# Power.net
KiCad netlist of a schematic drawn in Altium Designer
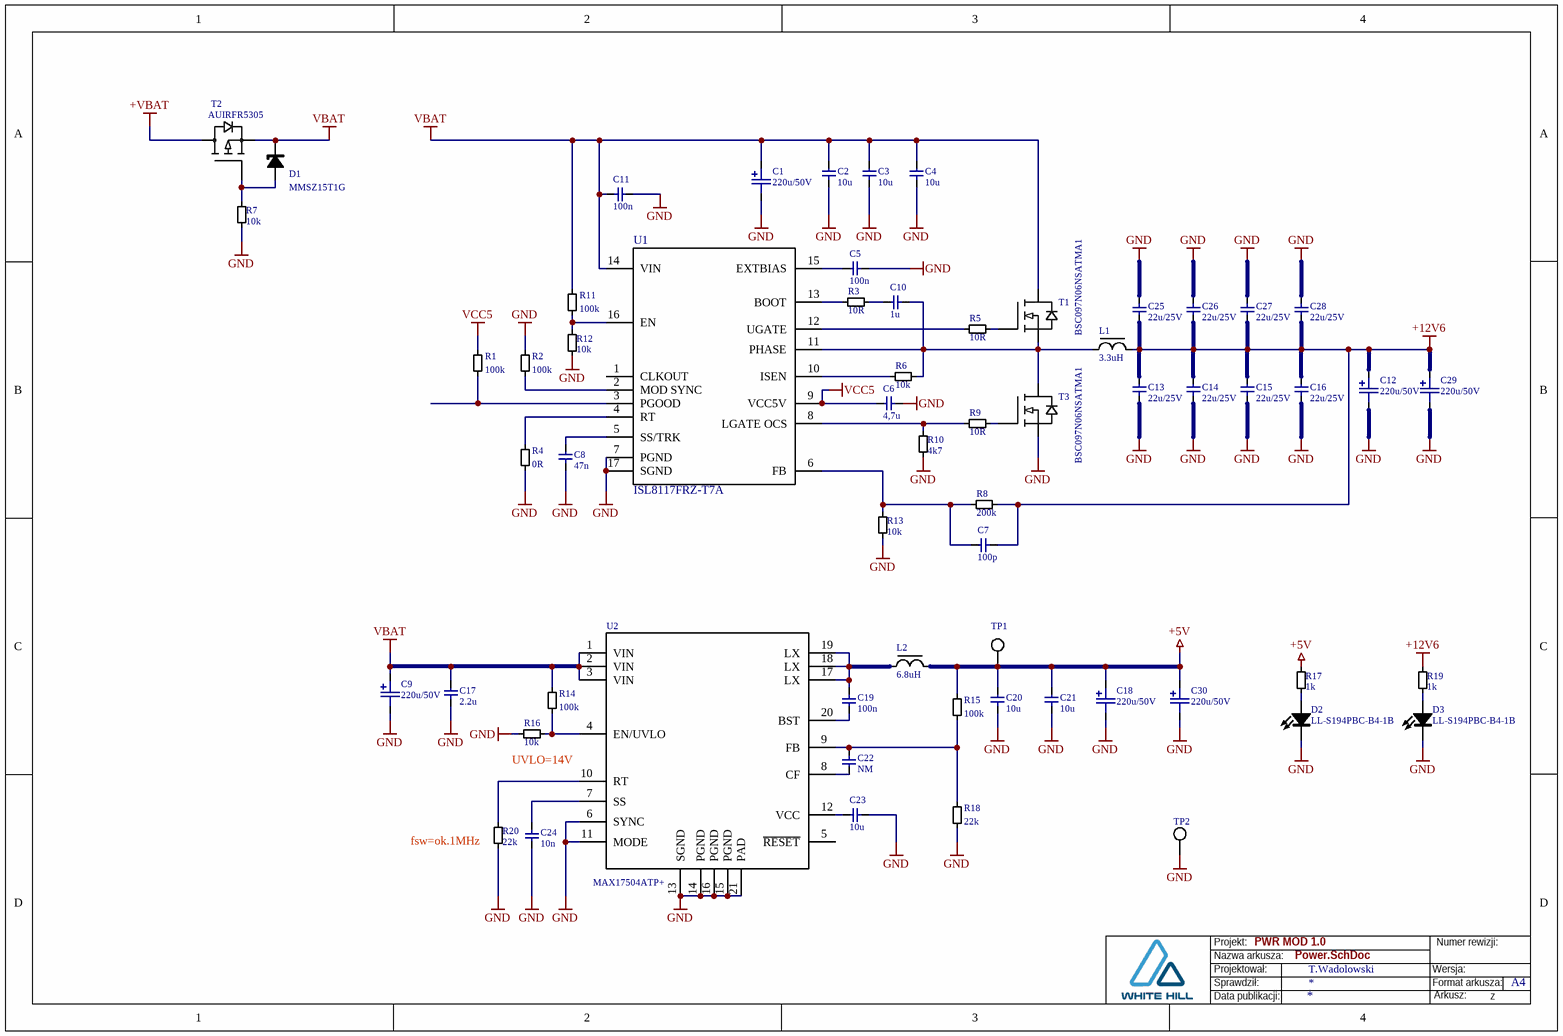
[diagram p0: Power.SchDoc]

(export (version "E")
  (design (tool "Eeschema 10.0.6"))
  (components
    (comp (ref "C1")
      (value "220u/50V")
      (footprint "ALU-G")
      (description "Capacitor: electrolytic; low impedance; 220uF; 50VDC; Case: G")
      (fields (field (name "MANUFACTURER") "Panasonic") (field (name "PART NUMBER") "EEEFP1H221AP"))
      (libsource (lib "WH") (part "CAP-EL"))
    )
    (comp (ref "C2")
      (value "10u")
      (footprint "C1206")
      (description "Capacitor: ceramic; 10uF; 50V; X7R; ±10%; SMD; 1206")
      (fields (field (name "MANUFACTURER") "Samnsung") (field (name "PART NUMBER") "CL31A106KBHNNNE"))
      (libsource (lib "CAPcer") (part "C-028"))
    )
    (comp (ref "C3")
      (value "10u")
      (footprint "C1206")
      (description "Capacitor: ceramic; 10uF; 50V; X7R; ±10%; SMD; 1206")
      (fields (field (name "MANUFACTURER") "Samnsung") (field (name "PART NUMBER") "CL31A106KBHNNNE"))
      (libsource (lib "CAPcer") (part "C-028"))
    )
    (comp (ref "C4")
      (value "10u")
      (footprint "C1206")
      (description "Capacitor: ceramic; 10uF; 50V; X7R; ±10%; SMD; 1206")
      (fields (field (name "MANUFACTURER") "Samnsung") (field (name "PART NUMBER") "CL31A106KBHNNNE"))
      (libsource (lib "CAPcer") (part "C-028"))
    )
    (comp (ref "C5")
      (value "100n")
      (footprint "C0603")
      (description "Capacitor: ceramic; 100nF; 50V; X7R; ±10%; SMD; 0603; Series: GRM")
      (fields (field (name "MANUFACTURER") "Murata") (field (name "PART NUMBER") "GRM188R71H104KA93D"))
      (libsource (lib "CAPcer") (part "C-013"))
    )
    (comp (ref "C6")
      (value "4,7u")
      (footprint "C0603")
      (description "Capacitor: ceramic;4,7uF ; 50V; X7R; ±5%; SMD; 0603")
      (fields (field (name "MANUFACTURER") "Samsung") (field (name "PART NUMBER") "0603X475K100CT"))
      (libsource (lib "CAPcer") (part "C-031"))
    )
    (comp (ref "C7")
      (value "100p")
      (footprint "C0603")
      (description "Capacitor: ceramic; MLCC; 100pF; 50V; C0G; ±1%; SMD; 0603")
      (fields (field (name "MANUFACTURER") "Vishay") (field (name "PART NUMBER") "VJ0603A101FXACW1BC"))
      (libsource (lib "CAPcer") (part "C-005"))
    )
    (comp (ref "C8")
      (value "47n")
      (footprint "C0603")
      (description "Capacitor: ceramic; MLCC; 47nF; 50V; X7R; ±10%; SMD; 0603")
      (fields (field (name "MANUFACTURER") "Kemet") (field (name "PART NUMBER") "C0603C473K5RACTU"))
      (libsource (lib "CAPcer") (part "C-012"))
    )
    (comp (ref "C9")
      (value "220u/50V")
      (footprint "ALU-G")
      (description "Capacitor: electrolytic; low impedance; 220uF; 50VDC; Case: G")
      (fields (field (name "MANUFACTURER") "Panasonic") (field (name "PART NUMBER") "EEEFP1H221AP"))
      (libsource (lib "WH") (part "CAP-EL"))
    )
    (comp (ref "C10")
      (value "1u")
      (footprint "C0805-10")
      (description "Capacitor: ceramic; MLCC; 1uF; 50V; X7R; SMD; 0805")
      (fields (field (name "MANUFACTURER") "Samsung") (field (name "PART NUMBER") "CL21B105KBFNNNG"))
      (libsource (lib "CAPcer") (part "C-017"))
    )
    (comp (ref "C11")
      (value "100n")
      (footprint "C0603")
      (description "Capacitor: ceramic; 100nF; 50V; X7R; ±10%; SMD; 0603; Series: GRM")
      (fields (field (name "MANUFACTURER") "Murata") (field (name "PART NUMBER") "GRM188R71H104KA93D"))
      (libsource (lib "CAPcer") (part "C-013"))
    )
    (comp (ref "C12")
      (value "220u/50V")
      (footprint "ALU-G")
      (description "Capacitor: electrolytic; low impedance; 220uF; 50VDC; Case: G")
      (fields (field (name "MANUFACTURER") "Panasonic") (field (name "PART NUMBER") "EEEFP1H221AP"))
      (libsource (lib "WH") (part "CAP-EL"))
    )
    (comp (ref "C13")
      (value "22u/25V")
      (footprint "C1206")
      (description "Capacitor: ceramic; 22uF; 25V; X7R; ±10%; SMD; 1206")
      (fields (field (name "MANUFACTURER") "Murata") (field (name "PART NUMBER") "GRM31CR61E226KE15L"))
      (libsource (lib "CAPcer") (part "C-029"))
    )
    (comp (ref "C14")
      (value "22u/25V")
      (footprint "C1206")
      (description "Capacitor: ceramic; 22uF; 25V; X7R; ±10%; SMD; 1206")
      (fields (field (name "MANUFACTURER") "Murata") (field (name "PART NUMBER") "GRM31CR61E226KE15L"))
      (libsource (lib "CAPcer") (part "C-029"))
    )
    (comp (ref "C15")
      (value "22u/25V")
      (footprint "C1206")
      (description "Capacitor: ceramic; 22uF; 25V; X7R; ±10%; SMD; 1206")
      (fields (field (name "MANUFACTURER") "Murata") (field (name "PART NUMBER") "GRM31CR61E226KE15L"))
      (libsource (lib "CAPcer") (part "C-029"))
    )
    (comp (ref "C16")
      (value "22u/25V")
      (footprint "C1206")
      (description "Capacitor: ceramic; 22uF; 25V; X7R; ±10%; SMD; 1206")
      (fields (field (name "MANUFACTURER") "Murata") (field (name "PART NUMBER") "GRM31CR61E226KE15L"))
      (libsource (lib "CAPcer") (part "C-029"))
    )
    (comp (ref "C17")
      (value "2.2u")
      (footprint "C1210")
      (description "Capacitor: ceramic; MLCC; 2,2uF; 100V; X7R; ±10%; SMD; 1210")
      (fields (field (name "MANUFACTURER") "Samnsung") (field (name "PART NUMBER") "CL32B225KCJSNNE"))
      (libsource (lib "CAPcer") (part "C-020"))
    )
    (comp (ref "C18")
      (value "220u/50V")
      (footprint "ALU-G")
      (description "Capacitor: electrolytic; low impedance; 220uF; 50VDC; Case: G")
      (fields (field (name "MANUFACTURER") "Panasonic") (field (name "PART NUMBER") "EEEFP1H221AP"))
      (libsource (lib "WH") (part "CAP-EL"))
    )
    (comp (ref "C19")
      (value "100n")
      (footprint "C0603")
      (description "Capacitor: ceramic; 100nF; 50V; X7R; ±10%; SMD; 0603; Series: GRM")
      (fields (field (name "MANUFACTURER") "Murata") (field (name "PART NUMBER") "GRM188R71H104KA93D"))
      (libsource (lib "CAPcer") (part "C-013"))
    )
    (comp (ref "C20")
      (value "10u")
      (footprint "C1206")
      (description "Capacitor: ceramic; 10uF; 35V; X7R; ±10%; SMD; 1206")
      (fields (field (name "MANUFACTURER") "Samnsung") (field (name "PART NUMBER") "CL31B106KLHNNNE"))
      (libsource (lib "CAPcer") (part "C-022"))
    )
    (comp (ref "C21")
      (value "10u")
      (footprint "C1206")
      (description "Capacitor: ceramic; 10uF; 35V; X7R; ±10%; SMD; 1206")
      (fields (field (name "MANUFACTURER") "Samnsung") (field (name "PART NUMBER") "CL31B106KLHNNNE"))
      (libsource (lib "CAPcer") (part "C-022"))
    )
    (comp (ref "C22")
      (value "NM")
      (footprint "C0603")
      (fields (field (name "MANUFACTURER") "Murata"))
      (libsource (lib "CAPcer") (part "C-013"))
    )
    (comp (ref "C23")
      (value "10u")
      (footprint "C0805-10")
      (description "Capacitor: ceramic; MLCC; 10uF; 16V; X5R; ±10%; SMD; 0805")
      (fields (field (name "MANUFACTURER") "Samnsung") (field (name "PART NUMBER") "CL21A106KOQNNNG"))
      (libsource (lib "CAPcer") (part "C-019"))
    )
    (comp (ref "C24")
      (value "10n")
      (footprint "C0603")
      (description "Capacitor: ceramic; MLCC; 10nF; 50V; X7R; ±5%; SMD; 0603")
      (fields (field (name "MANUFACTURER") "Vishay") (field (name "PART NUMBER") "VJ0603Y103JXACW1BC"))
      (libsource (lib "CAPcer") (part "C-011"))
    )
    (comp (ref "C25")
      (value "22u/25V")
      (footprint "C1206")
      (description "Capacitor: ceramic; 22uF; 25V; X7R; ±10%; SMD; 1206")
      (fields (field (name "MANUFACTURER") "Murata") (field (name "PART NUMBER") "GRM31CR61E226KE15L"))
      (libsource (lib "CAPcer") (part "C-029"))
    )
    (comp (ref "C26")
      (value "22u/25V")
      (footprint "C1206")
      (description "Capacitor: ceramic; 22uF; 25V; X7R; ±10%; SMD; 1206")
      (fields (field (name "MANUFACTURER") "Murata") (field (name "PART NUMBER") "GRM31CR61E226KE15L"))
      (libsource (lib "CAPcer") (part "C-029"))
    )
    (comp (ref "C27")
      (value "22u/25V")
      (footprint "C1206")
      (description "Capacitor: ceramic; 22uF; 25V; X7R; ±10%; SMD; 1206")
      (fields (field (name "MANUFACTURER") "Murata") (field (name "PART NUMBER") "GRM31CR61E226KE15L"))
      (libsource (lib "CAPcer") (part "C-029"))
    )
    (comp (ref "C28")
      (value "22u/25V")
      (footprint "C1206")
      (description "Capacitor: ceramic; 22uF; 25V; X7R; ±10%; SMD; 1206")
      (fields (field (name "MANUFACTURER") "Murata") (field (name "PART NUMBER") "GRM31CR61E226KE15L"))
      (libsource (lib "CAPcer") (part "C-029"))
    )
    (comp (ref "C29")
      (value "220u/50V")
      (footprint "ALU-G")
      (description "Capacitor: electrolytic; low impedance; 220uF; 50VDC; Case: G")
      (fields (field (name "MANUFACTURER") "Panasonic") (field (name "PART NUMBER") "EEEFP1H221AP"))
      (libsource (lib "WH") (part "CAP-EL"))
    )
    (comp (ref "C30")
      (value "220u/50V")
      (footprint "ALU-G")
      (description "Capacitor: electrolytic; low impedance; 220uF; 50VDC; Case: G")
      (fields (field (name "MANUFACTURER") "Panasonic") (field (name "PART NUMBER") "EEEFP1H221AP"))
      (libsource (lib "WH") (part "CAP-EL"))
    )
    (comp (ref "D1")
      (value "MMSZ15T1G")
      (footprint "SOD123")
      (description "Dioda: Zenera; 0,5W; 18V; SMD")
      (fields (field (name "MANUFACTURER") "ON Semi"))
      (libsource (lib "DGI") (part "D_ZEN"))
    )
    (comp (ref "D2")
      (value "LL-S194PBC-B4-1B")
      (footprint "LED0603B")
      (description "LED; SMD; 0603; blue; 20-40mcd; 1.6x0.8x0.4mm; 130°; 2.8÷3.8V; 20mA")
      (fields (field (name "MANUFACTURER") "LuckyLight"))
      (libsource (lib "DGI") (part "LED_1"))
    )
    (comp (ref "D3")
      (value "LL-S194PBC-B4-1B")
      (footprint "LED0603B")
      (description "LED; SMD; 0603; blue; 20-40mcd; 1.6x0.8x0.4mm; 130°; 2.8÷3.8V; 20mA")
      (fields (field (name "MANUFACTURER") "LuckyLight"))
      (libsource (lib "DGI") (part "LED_1"))
    )
    (comp (ref "L1")
      (value "3.3uH")
      (footprint "HPI1260")
      (description "Inductor: wire; SMD; 3.3uH; Ioper:14A; 2.45mOhm; ±20%; Isat:15A")
      (fields (field (name "MANUFACTURER") "Ferrocore") (field (name "PART NUMBER") "HPI1260-3R3"))
      (libsource (lib "WH") (part "L_HPI_3.3uH"))
    )
    (comp (ref "L2")
      (value "6.8uH")
      (footprint "L 7x7")
      (description "Inductor: wire; SMD; 6.8uH; Ioper:4.3A; 53mΩ; ±20%; Isat:4.9A")
      (fields (field (name "MANUFACTURER") "Ferrocore") (field (name "PART NUMBER") "HPI0630-6R8"))
      (libsource (lib "DGI") (part "L"))
    )
    (comp (ref "R1")
      (value "100k")
      (footprint "R0603")
      (description "Resistor: thick film; SMD; 0603; 100k; 0.125W; ±5%")
      (fields (field (name "MANUFACTURER") "Walsin") (field (name "PART NUMBER") "WF06P104JTL"))
      (libsource (lib "Resistors") (part "R-013"))
    )
    (comp (ref "R2")
      (value "100k")
      (footprint "R0603")
      (description "Resistor: thick film; SMD; 0603; 100k; 0.125W; ±5%")
      (fields (field (name "MANUFACTURER") "Walsin") (field (name "PART NUMBER") "WF06P104JTL"))
      (libsource (lib "Resistors") (part "R-013"))
    )
    (comp (ref "R3")
      (value "10R")
      (footprint "R0603")
      (description "Resistor: thick film; SMD; 0603; 10R; 0.1W; ±5%")
      (fields (field (name "MANUFACTURER") "Royal Ohm") (field (name "PART NUMBER") "0603SAJ0100T5E"))
      (libsource (lib "Resistors") (part "R-001"))
    )
    (comp (ref "R4")
      (value "0R")
      (footprint "R0603")
      (description "Resistor: thick film; SMD; 0603; 0R; 0.125W; ±5%")
      (fields (field (name "MANUFACTURER") "Royal Ohm") (field (name "PART NUMBER") "CRCW06030000Z0TABC"))
      (libsource (lib "Resistors") (part "R-018"))
    )
    (comp (ref "R5")
      (value "10R")
      (footprint "R0603")
      (description "Resistor: thick film; SMD; 0603; 10R; 0.1W; ±5%")
      (fields (field (name "MANUFACTURER") "Royal Ohm") (field (name "PART NUMBER") "0603SAJ0100T5E"))
      (libsource (lib "Resistors") (part "R-001"))
    )
    (comp (ref "R6")
      (value "10k")
      (footprint "R0603")
      (description "Resistor: thick film; SMD; 0603; 10k; 0.125W; ±5%")
      (fields (field (name "MANUFACTURER") "Walsin") (field (name "PART NUMBER") "WF06P103JTL"))
      (libsource (lib "") (part "R-012_2"))
    )
    (comp (ref "R7")
      (value "10k")
      (footprint "R0603")
      (description "Resistor: thick film; SMD; 0603; 10k; 0.125W; ±5%")
      (fields (field (name "MANUFACTURER") "Walsin") (field (name "PART NUMBER") "WF06P103JTL"))
      (libsource (lib "") (part "R-012_1"))
    )
    (comp (ref "R8")
      (value "200k")
      (footprint "R0603")
      (description "Resistor: thick film; SMD; 0805; 200k; 0.125W; ±5%;")
      (fields (field (name "MANUFACTURER") "Royal Ohm") (field (name "PART NUMBER") "0603SAJ0204T5E"))
      (libsource (lib "Resistors") (part "R-042"))
    )
    (comp (ref "R9")
      (value "10R")
      (footprint "R0603")
      (description "Resistor: thick film; SMD; 0603; 10R; 0.1W; ±5%")
      (fields (field (name "MANUFACTURER") "Royal Ohm") (field (name "PART NUMBER") "0603SAJ0100T5E"))
      (libsource (lib "Resistors") (part "R-001"))
    )
    (comp (ref "R10")
      (value "4k7")
      (footprint "R0603")
      (description "Resistor: thick film; SMD; 0603; 4.7k; 0.125W; ±5%")
      (fields (field (name "MANUFACTURER") "Walsin") (field (name "PART NUMBER") "WF06P472JTL"))
      (libsource (lib "Resistors") (part "R-011"))
    )
    (comp (ref "R11")
      (value "100k")
      (footprint "R0603")
      (description "Resistor: thick film; SMD; 0603; 100k; 0.125W; ±5%")
      (fields (field (name "MANUFACTURER") "Walsin") (field (name "PART NUMBER") "WF06P104JTL"))
      (libsource (lib "Resistors") (part "R-013"))
    )
    (comp (ref "R12")
      (value "10k")
      (footprint "R0603")
      (description "Resistor: thick film; SMD; 0603; 10k; 0.125W; ±5%")
      (fields (field (name "MANUFACTURER") "Walsin") (field (name "PART NUMBER") "WF06P103JTL"))
      (libsource (lib "") (part "R-012_1"))
    )
    (comp (ref "R13")
      (value "10k")
      (footprint "R0603")
      (description "Resistor: thick film; SMD; 0603; 10k; 0.125W; ±5%")
      (fields (field (name "MANUFACTURER") "Walsin") (field (name "PART NUMBER") "WF06P103JTL"))
      (libsource (lib "") (part "R-012_1"))
    )
    (comp (ref "R14")
      (value "100k")
      (footprint "R0603")
      (description "Resistor: thick film; SMD; 0603; 100k; 0.125W; ±5%")
      (fields (field (name "MANUFACTURER") "Walsin") (field (name "PART NUMBER") "WF06P104JTL"))
      (libsource (lib "Resistors") (part "R-013"))
    )
    (comp (ref "R15")
      (value "100k")
      (footprint "R0603")
      (description "Resistor: thick film; SMD; 0603; 100k; 0.125W; ±5%")
      (fields (field (name "MANUFACTURER") "Walsin") (field (name "PART NUMBER") "WF06P104JTL"))
      (libsource (lib "Resistors") (part "R-013"))
    )
    (comp (ref "R16")
      (value "10k")
      (footprint "R0603")
      (description "Resistor: thick film; SMD; 0603; 10k; 0.125W; ±5%")
      (fields (field (name "MANUFACTURER") "Walsin") (field (name "PART NUMBER") "WF06P103JTL"))
      (libsource (lib "Resistors") (part "R-012"))
    )
    (comp (ref "R17")
      (value "1k")
      (footprint "R0603")
      (description "Resistor: thick film; SMD; 0603; 1k; 0.1W; ±5%")
      (fields (field (name "MANUFACTURER") "Royal Ohm") (field (name "PART NUMBER") "0603SAJ0102T5E"))
      (libsource (lib "Resistors") (part "R-005"))
    )
    (comp (ref "R18")
      (value "22k")
      (footprint "R0603")
      (description "Resistor: thick film; SMD; 0603; 22k; 0.1W; ±5%;")
      (fields (field (name "MANUFACTURER") "Royal Ohm") (field (name "PART NUMBER") "SMD0603-22K"))
      (libsource (lib "Resistors") (part "R-027"))
    )
    (comp (ref "R19")
      (value "1k")
      (footprint "R0603")
      (description "Resistor: thick film; SMD; 0603; 1k; 0.1W; ±5%")
      (fields (field (name "MANUFACTURER") "Royal Ohm") (field (name "PART NUMBER") "0603SAJ0102T5E"))
      (libsource (lib "Resistors") (part "R-005"))
    )
    (comp (ref "R20")
      (value "22k")
      (footprint "R0603")
      (description "Resistor: thick film; SMD; 0603; 22k; 0.1W; ±5%;")
      (fields (field (name "MANUFACTURER") "Royal Ohm") (field (name "PART NUMBER") "SMD0603-22K"))
      (libsource (lib "Resistors") (part "R-027"))
    )
    (comp (ref "T1")
      (value "BSC097N06NSATMA1")
      (footprint "PowerPAK SO-8")
      (description "Transistor N MOS 60V;10 mOhm;46A")
      (fields (field (name "MANUFACTURER") "Infineon"))
      (libsource (lib "WH") (part "NVMFS5C426NAFT1G"))
    )
    (comp (ref "T2")
      (value "AUIRFR5305")
      (footprint "DPAK")
      (description "Transistor: P-MOSFET; unipolar; -55V; -31A; 110W; DPAK")
      (fields (field (name "MANUFACTURER") "IR"))
      (libsource (lib "DGI") (part "IRFR5410PBF"))
    )
    (comp (ref "T3")
      (value "BSC097N06NSATMA1")
      (footprint "PowerPAK SO-8")
      (description "Transistor N MOS 60V;10 mOhm;46A")
      (fields (field (name "MANUFACTURER") "Infineon"))
      (libsource (lib "WH") (part "NVMFS5C426NAFT1G"))
    )
    (comp (ref "TP1")
      (value "TP")
      (footprint "TP")
      (description "Test point")
      (libsource (lib "DGI") (part "TP"))
    )
    (comp (ref "TP2")
      (value "TEST-1R")
      (footprint "TP-O")
      (description "Sprezynka pomiarowa czerwona")
      (libsource (lib "WH") (part "TP_O"))
    )
    (comp (ref "U1")
      (value "ISL8117FRZ-T7A")
      (footprint "QFN-16-0.5")
      (description "Synchronous Step-Down PWM Controller 60V 2MHz")
      (fields (field (name "MANUFACTURER") "Renesas"))
      (libsource (lib "WH") (part "ISL8117"))
    )
    (comp (ref "U2")
      (value "MAX17504ATP+")
      (footprint "TQFN-20_5x5")
      (description "4.5V–60V, 3.5A, High-Efficiency, Synchronous  Step-Down DC-DC Converter")
      (fields (field (name "MANUFACTURER") "Maxim") (field (name "PART NUMBER") "MAX6143AASA10+"))
      (libsource (lib "WH") (part "MAX17503"))
    )
  )
  (nets
    (net (code "1") (name "+5V") (class "Default")
      (node (ref "C18") (pin "1") (pinfunction "1_1") (pintype "passive"))
      (node (ref "C20") (pin "1") (pinfunction "1_1") (pintype "passive"))
      (node (ref "C21") (pin "1") (pinfunction "1_1") (pintype "passive"))
      (node (ref "C30") (pin "1") (pinfunction "1_1") (pintype "passive"))
      (node (ref "L2") (pin "2") (pinfunction "2_2") (pintype "passive"))
      (node (ref "R15") (pin "2") (pinfunction "BOT_2") (pintype "passive"))
      (node (ref "R17") (pin "1") (pinfunction "TOP_1") (pintype "passive"))
      (node (ref "TP1") (pin "1") (pinfunction "1_1") (pintype "passive"))
    )
    (net (code "2") (name "+12V6") (class "Default")
      (node (ref "C12") (pin "1") (pinfunction "1_1") (pintype "passive"))
      (node (ref "C13") (pin "1") (pinfunction "1_1") (pintype "passive"))
      (node (ref "C14") (pin "1") (pinfunction "1_1") (pintype "passive"))
      (node (ref "C15") (pin "1") (pinfunction "1_1") (pintype "passive"))
      (node (ref "C16") (pin "1") (pinfunction "1_1") (pintype "passive"))
      (node (ref "C25") (pin "1") (pinfunction "1_1") (pintype "passive"))
      (node (ref "C26") (pin "1") (pinfunction "1_1") (pintype "passive"))
      (node (ref "C27") (pin "1") (pinfunction "1_1") (pintype "passive"))
      (node (ref "C28") (pin "1") (pinfunction "1_1") (pintype "passive"))
      (node (ref "C29") (pin "1") (pinfunction "1_1") (pintype "passive"))
      (node (ref "C7") (pin "2") (pinfunction "2_2") (pintype "passive"))
      (node (ref "L1") (pin "2") (pinfunction "2_2") (pintype "passive"))
      (node (ref "R19") (pin "1") (pinfunction "TOP_1") (pintype "passive"))
      (node (ref "R8") (pin "1") (pinfunction "TOP_1") (pintype "passive"))
    )
    (net (code "3") (name "+VBAT") (class "Default")
      (node (ref "T2") (pin "2") (pinfunction "D_2") (pintype "passive"))
    )
    (net (code "4") (name "GND") (class "Default")
      (node (ref "C1") (pin "2") (pinfunction "2_2") (pintype "passive"))
      (node (ref "C11") (pin "1") (pinfunction "1_1") (pintype "passive"))
      (node (ref "C12") (pin "2") (pinfunction "2_2") (pintype "passive"))
      (node (ref "C13") (pin "2") (pinfunction "2_2") (pintype "passive"))
      (node (ref "C14") (pin "2") (pinfunction "2_2") (pintype "passive"))
      (node (ref "C15") (pin "2") (pinfunction "2_2") (pintype "passive"))
      (node (ref "C16") (pin "2") (pinfunction "2_2") (pintype "passive"))
      (node (ref "C17") (pin "2") (pinfunction "2_2") (pintype "passive"))
      (node (ref "C18") (pin "2") (pinfunction "2_2") (pintype "passive"))
      (node (ref "C2") (pin "2") (pinfunction "2_2") (pintype "passive"))
      (node (ref "C20") (pin "2") (pinfunction "2_2") (pintype "passive"))
      (node (ref "C21") (pin "2") (pinfunction "2_2") (pintype "passive"))
      (node (ref "C23") (pin "2") (pinfunction "2_2") (pintype "passive"))
      (node (ref "C24") (pin "1") (pinfunction "1_1") (pintype "passive"))
      (node (ref "C25") (pin "2") (pinfunction "2_2") (pintype "passive"))
      (node (ref "C26") (pin "2") (pinfunction "2_2") (pintype "passive"))
      (node (ref "C27") (pin "2") (pinfunction "2_2") (pintype "passive"))
      (node (ref "C28") (pin "2") (pinfunction "2_2") (pintype "passive"))
      (node (ref "C29") (pin "2") (pinfunction "2_2") (pintype "passive"))
      (node (ref "C3") (pin "2") (pinfunction "2_2") (pintype "passive"))
      (node (ref "C30") (pin "2") (pinfunction "2_2") (pintype "passive"))
      (node (ref "C4") (pin "2") (pinfunction "2_2") (pintype "passive"))
      (node (ref "C5") (pin "2") (pinfunction "2_2") (pintype "passive"))
      (node (ref "C6") (pin "2") (pinfunction "2_2") (pintype "passive"))
      (node (ref "C8") (pin "2") (pinfunction "2_2") (pintype "passive"))
      (node (ref "C9") (pin "2") (pinfunction "2_2") (pintype "passive"))
      (node (ref "D2") (pin "K") (pinfunction "K_K") (pintype "passive"))
      (node (ref "D3") (pin "K") (pinfunction "K_K") (pintype "passive"))
      (node (ref "R10") (pin "1") (pinfunction "TOP_1") (pintype "passive"))
      (node (ref "R12") (pin "2") (pinfunction "BOT_2") (pintype "passive"))
      (node (ref "R13") (pin "2") (pinfunction "BOT_2") (pintype "passive"))
      (node (ref "R16") (pin "1") (pinfunction "TOP_1") (pintype "passive"))
      (node (ref "R18") (pin "2") (pinfunction "BOT_2") (pintype "passive"))
      (node (ref "R2") (pin "2") (pinfunction "BOT_2") (pintype "passive"))
      (node (ref "R20") (pin "2") (pinfunction "BOT_2") (pintype "passive"))
      (node (ref "R4") (pin "2") (pinfunction "BOT_2") (pintype "passive"))
      (node (ref "R7") (pin "2") (pinfunction "BOT_2") (pintype "passive"))
      (node (ref "T3") (pin "S") (pinfunction "S_S") (pintype "passive"))
      (node (ref "TP2") (pin "1") (pinfunction "1_1") (pintype "passive"))
      (node (ref "U1") (pin "17") (pinfunction "SGND_17") (pintype "passive"))
      (node (ref "U1") (pin "7") (pinfunction "PGND_7") (pintype "passive"))
      (node (ref "U2") (pin "11") (pinfunction "MODE_11") (pintype "passive"))
      (node (ref "U2") (pin "13") (pinfunction "SGND_13") (pintype "passive"))
      (node (ref "U2") (pin "14") (pinfunction "PGND_14") (pintype "passive"))
      (node (ref "U2") (pin "15") (pinfunction "PGND_15") (pintype "passive"))
      (node (ref "U2") (pin "16") (pinfunction "PGND_16") (pintype "passive"))
      (node (ref "U2") (pin "21") (pinfunction "PAD_21") (pintype "passive"))
      (node (ref "U2") (pin "6") (pinfunction "SYNC_6") (pintype "passive"))
    )
    (net (code "5") (name "Net-(C19-Pad2)") (class "Default")
      (node (ref "C19") (pin "2") (pinfunction "2_2") (pintype "passive"))
      (node (ref "L2") (pin "1") (pinfunction "1_1") (pintype "passive"))
      (node (ref "U2") (pin "17") (pinfunction "LX_17") (pintype "passive"))
      (node (ref "U2") (pin "18") (pinfunction "LX_18") (pintype "passive"))
      (node (ref "U2") (pin "19") (pinfunction "LX_19") (pintype "passive"))
    )
    (net (code "6") (name "Net-(D1-A)") (class "Default")
      (node (ref "D1") (pin "1") (pinfunction "A_1") (pintype "passive"))
      (node (ref "R7") (pin "1") (pinfunction "TOP_1") (pintype "passive"))
      (node (ref "T2") (pin "1") (pinfunction "G_1") (pintype "passive"))
    )
    (net (code "7") (name "Net-(R1-TOP)") (class "Default")
      (node (ref "R1") (pin "1") (pinfunction "TOP_1") (pintype "passive"))
      (node (ref "U1") (pin "3") (pinfunction "PGOOD_3") (pintype "passive"))
    )
    (net (code "8") (name "Net-(R2-TOP)") (class "Default")
      (node (ref "R2") (pin "1") (pinfunction "TOP_1") (pintype "passive"))
      (node (ref "U1") (pin "2") (pinfunction "MOD_SYNC_2") (pintype "passive"))
    )
    (net (code "9") (name "Net-(R3-BOT)") (class "Default")
      (node (ref "R3") (pin "2") (pinfunction "BOT_2") (pintype "passive"))
      (node (ref "U1") (pin "13") (pinfunction "BOOT_13") (pintype "passive"))
    )
    (net (code "10") (name "Net-(R3-TOP)") (class "Default")
      (node (ref "C10") (pin "1") (pinfunction "1_1") (pintype "passive"))
      (node (ref "R3") (pin "1") (pinfunction "TOP_1") (pintype "passive"))
    )
    (net (code "11") (name "Net-(R4-TOP)") (class "Default")
      (node (ref "R4") (pin "1") (pinfunction "TOP_1") (pintype "passive"))
      (node (ref "U1") (pin "4") (pinfunction "RT_4") (pintype "passive"))
    )
    (net (code "12") (name "Net-(R5-BOT)") (class "Default")
      (node (ref "R5") (pin "2") (pinfunction "BOT_2") (pintype "passive"))
      (node (ref "U1") (pin "12") (pinfunction "UGATE_12") (pintype "passive"))
    )
    (net (code "13") (name "Net-(R5-TOP)") (class "Default")
      (node (ref "R5") (pin "1") (pinfunction "TOP_1") (pintype "passive"))
      (node (ref "T1") (pin "G") (pinfunction "G_G") (pintype "passive"))
    )
    (net (code "14") (name "Net-(R6-BOT)") (class "Default")
      (node (ref "R6") (pin "2") (pinfunction "BOT_2") (pintype "passive"))
      (node (ref "U1") (pin "10") (pinfunction "ISEN_10") (pintype "passive"))
    )
    (net (code "15") (name "Net-(R6-TOP)") (class "Default")
      (node (ref "C10") (pin "2") (pinfunction "2_2") (pintype "passive"))
      (node (ref "L1") (pin "1") (pinfunction "1_1") (pintype "passive"))
      (node (ref "R6") (pin "1") (pinfunction "TOP_1") (pintype "passive"))
      (node (ref "T1") (pin "S") (pinfunction "S_S") (pintype "passive"))
      (node (ref "T3") (pin "D") (pinfunction "D_D") (pintype "passive"))
      (node (ref "U1") (pin "11") (pinfunction "PHASE_11") (pintype "passive"))
    )
    (net (code "16") (name "Net-(R9-TOP)") (class "Default")
      (node (ref "R9") (pin "1") (pinfunction "TOP_1") (pintype "passive"))
      (node (ref "T3") (pin "G") (pinfunction "G_G") (pintype "passive"))
    )
    (net (code "17") (name "Net-(R10-BOT)") (class "Default")
      (node (ref "R10") (pin "2") (pinfunction "BOT_2") (pintype "passive"))
      (node (ref "R9") (pin "2") (pinfunction "BOT_2") (pintype "passive"))
      (node (ref "U1") (pin "8") (pinfunction "LGATE_OCS_8") (pintype "passive"))
    )
    (net (code "18") (name "Net-(R11-TOP)") (class "Default")
      (node (ref "R11") (pin "1") (pinfunction "TOP_1") (pintype "passive"))
      (node (ref "R12") (pin "1") (pinfunction "TOP_1") (pintype "passive"))
      (node (ref "U1") (pin "16") (pinfunction "EN_16") (pintype "passive"))
    )
    (net (code "19") (name "Net-(R13-TOP)") (class "Default")
      (node (ref "C7") (pin "1") (pinfunction "1_1") (pintype "passive"))
      (node (ref "R13") (pin "1") (pinfunction "TOP_1") (pintype "passive"))
      (node (ref "R8") (pin "2") (pinfunction "BOT_2") (pintype "passive"))
      (node (ref "U1") (pin "6") (pinfunction "FB_6") (pintype "passive"))
    )
    (net (code "20") (name "Net-(R14-TOP)") (class "Default")
      (node (ref "R14") (pin "1") (pinfunction "TOP_1") (pintype "passive"))
      (node (ref "R16") (pin "2") (pinfunction "BOT_2") (pintype "passive"))
      (node (ref "U2") (pin "4") (pinfunction "EN/UVLO_4") (pintype "passive"))
    )
    (net (code "21") (name "Net-(R15-TOP)") (class "Default")
      (node (ref "C22") (pin "2") (pinfunction "2_2") (pintype "passive"))
      (node (ref "R15") (pin "1") (pinfunction "TOP_1") (pintype "passive"))
      (node (ref "R18") (pin "1") (pinfunction "TOP_1") (pintype "passive"))
      (node (ref "U2") (pin "9") (pinfunction "FB_9") (pintype "passive"))
    )
    (net (code "22") (name "Net-(R17-BOT)") (class "Default")
      (node (ref "D2") (pin "A") (pinfunction "A_A") (pintype "passive"))
      (node (ref "R17") (pin "2") (pinfunction "BOT_2") (pintype "passive"))
    )
    (net (code "23") (name "Net-(R19-BOT)") (class "Default")
      (node (ref "D3") (pin "A") (pinfunction "A_A") (pintype "passive"))
      (node (ref "R19") (pin "2") (pinfunction "BOT_2") (pintype "passive"))
    )
    (net (code "24") (name "Net-(R20-TOP)") (class "Default")
      (node (ref "R20") (pin "1") (pinfunction "TOP_1") (pintype "passive"))
      (node (ref "U2") (pin "10") (pinfunction "RT_10") (pintype "passive"))
    )
    (net (code "25") (name "Net-(U1-EXTBIAS)") (class "Default")
      (node (ref "C5") (pin "1") (pinfunction "1_1") (pintype "passive"))
      (node (ref "U1") (pin "15") (pinfunction "EXTBIAS_15") (pintype "power_in"))
    )
    (net (code "26") (name "Net-(U1-SS{slash}TRK)") (class "Default")
      (node (ref "C8") (pin "1") (pinfunction "1_1") (pintype "passive"))
      (node (ref "U1") (pin "5") (pinfunction "SS/TRK_5") (pintype "passive"))
    )
    (net (code "27") (name "Net-(U2-BST)") (class "Default")
      (node (ref "C19") (pin "1") (pinfunction "1_1") (pintype "passive"))
      (node (ref "U2") (pin "20") (pinfunction "BST_20") (pintype "passive"))
    )
    (net (code "28") (name "Net-(U2-CF)") (class "Default")
      (node (ref "C22") (pin "1") (pinfunction "1_1") (pintype "passive"))
      (node (ref "U2") (pin "8") (pinfunction "CF_8") (pintype "passive"))
    )
    (net (code "29") (name "Net-(U2-SS)") (class "Default")
      (node (ref "C24") (pin "2") (pinfunction "2_2") (pintype "passive"))
      (node (ref "U2") (pin "7") (pinfunction "SS_7") (pintype "passive"))
    )
    (net (code "30") (name "Net-(U2-VCC)") (class "Default")
      (node (ref "C23") (pin "1") (pinfunction "1_1") (pintype "passive"))
      (node (ref "U2") (pin "12") (pinfunction "VCC_12") (pintype "passive"))
    )
    (net (code "31") (name "VBAT") (class "Default")
      (node (ref "C1") (pin "1") (pinfunction "1_1") (pintype "passive"))
      (node (ref "C11") (pin "2") (pinfunction "2_2") (pintype "passive"))
      (node (ref "C17") (pin "1") (pinfunction "1_1") (pintype "passive"))
      (node (ref "C2") (pin "1") (pinfunction "1_1") (pintype "passive"))
      (node (ref "C3") (pin "1") (pinfunction "1_1") (pintype "passive"))
      (node (ref "C4") (pin "1") (pinfunction "1_1") (pintype "passive"))
      (node (ref "C9") (pin "1") (pinfunction "1_1") (pintype "passive"))
      (node (ref "D1") (pin "2") (pinfunction "K_2") (pintype "passive"))
      (node (ref "R11") (pin "2") (pinfunction "BOT_2") (pintype "passive"))
      (node (ref "R14") (pin "2") (pinfunction "BOT_2") (pintype "passive"))
      (node (ref "T1") (pin "D") (pinfunction "D_D") (pintype "passive"))
      (node (ref "T2") (pin "3") (pinfunction "S_3") (pintype "passive"))
      (node (ref "U1") (pin "14") (pinfunction "VIN_14") (pintype "passive"))
      (node (ref "U2") (pin "1") (pinfunction "VIN_1") (pintype "passive"))
      (node (ref "U2") (pin "2") (pinfunction "VIN_2") (pintype "passive"))
      (node (ref "U2") (pin "3") (pinfunction "VIN_3") (pintype "passive"))
    )
    (net (code "32") (name "VCC5") (class "Default")
      (node (ref "C6") (pin "1") (pinfunction "1_1") (pintype "passive"))
      (node (ref "R1") (pin "2") (pinfunction "BOT_2") (pintype "passive"))
      (node (ref "U1") (pin "9") (pinfunction "VCC5V_9") (pintype "passive"))
    )
    (net (code "33") (name "unconnected-(U1-CLKOUT-Pad1)") (class "Default")
      (node (ref "U1") (pin "1") (pinfunction "CLKOUT_1") (pintype "passive"))
    )
    (net (code "34") (name "unconnected-(U2-~{RESET}-Pad5)") (class "Default")
      (node (ref "U2") (pin "5") (pinfunction "~{RESET}_5") (pintype "passive"))
    )
  )
)
